# bristol_longshot.net
KiCad netlist of a schematic drawn in EAGLE
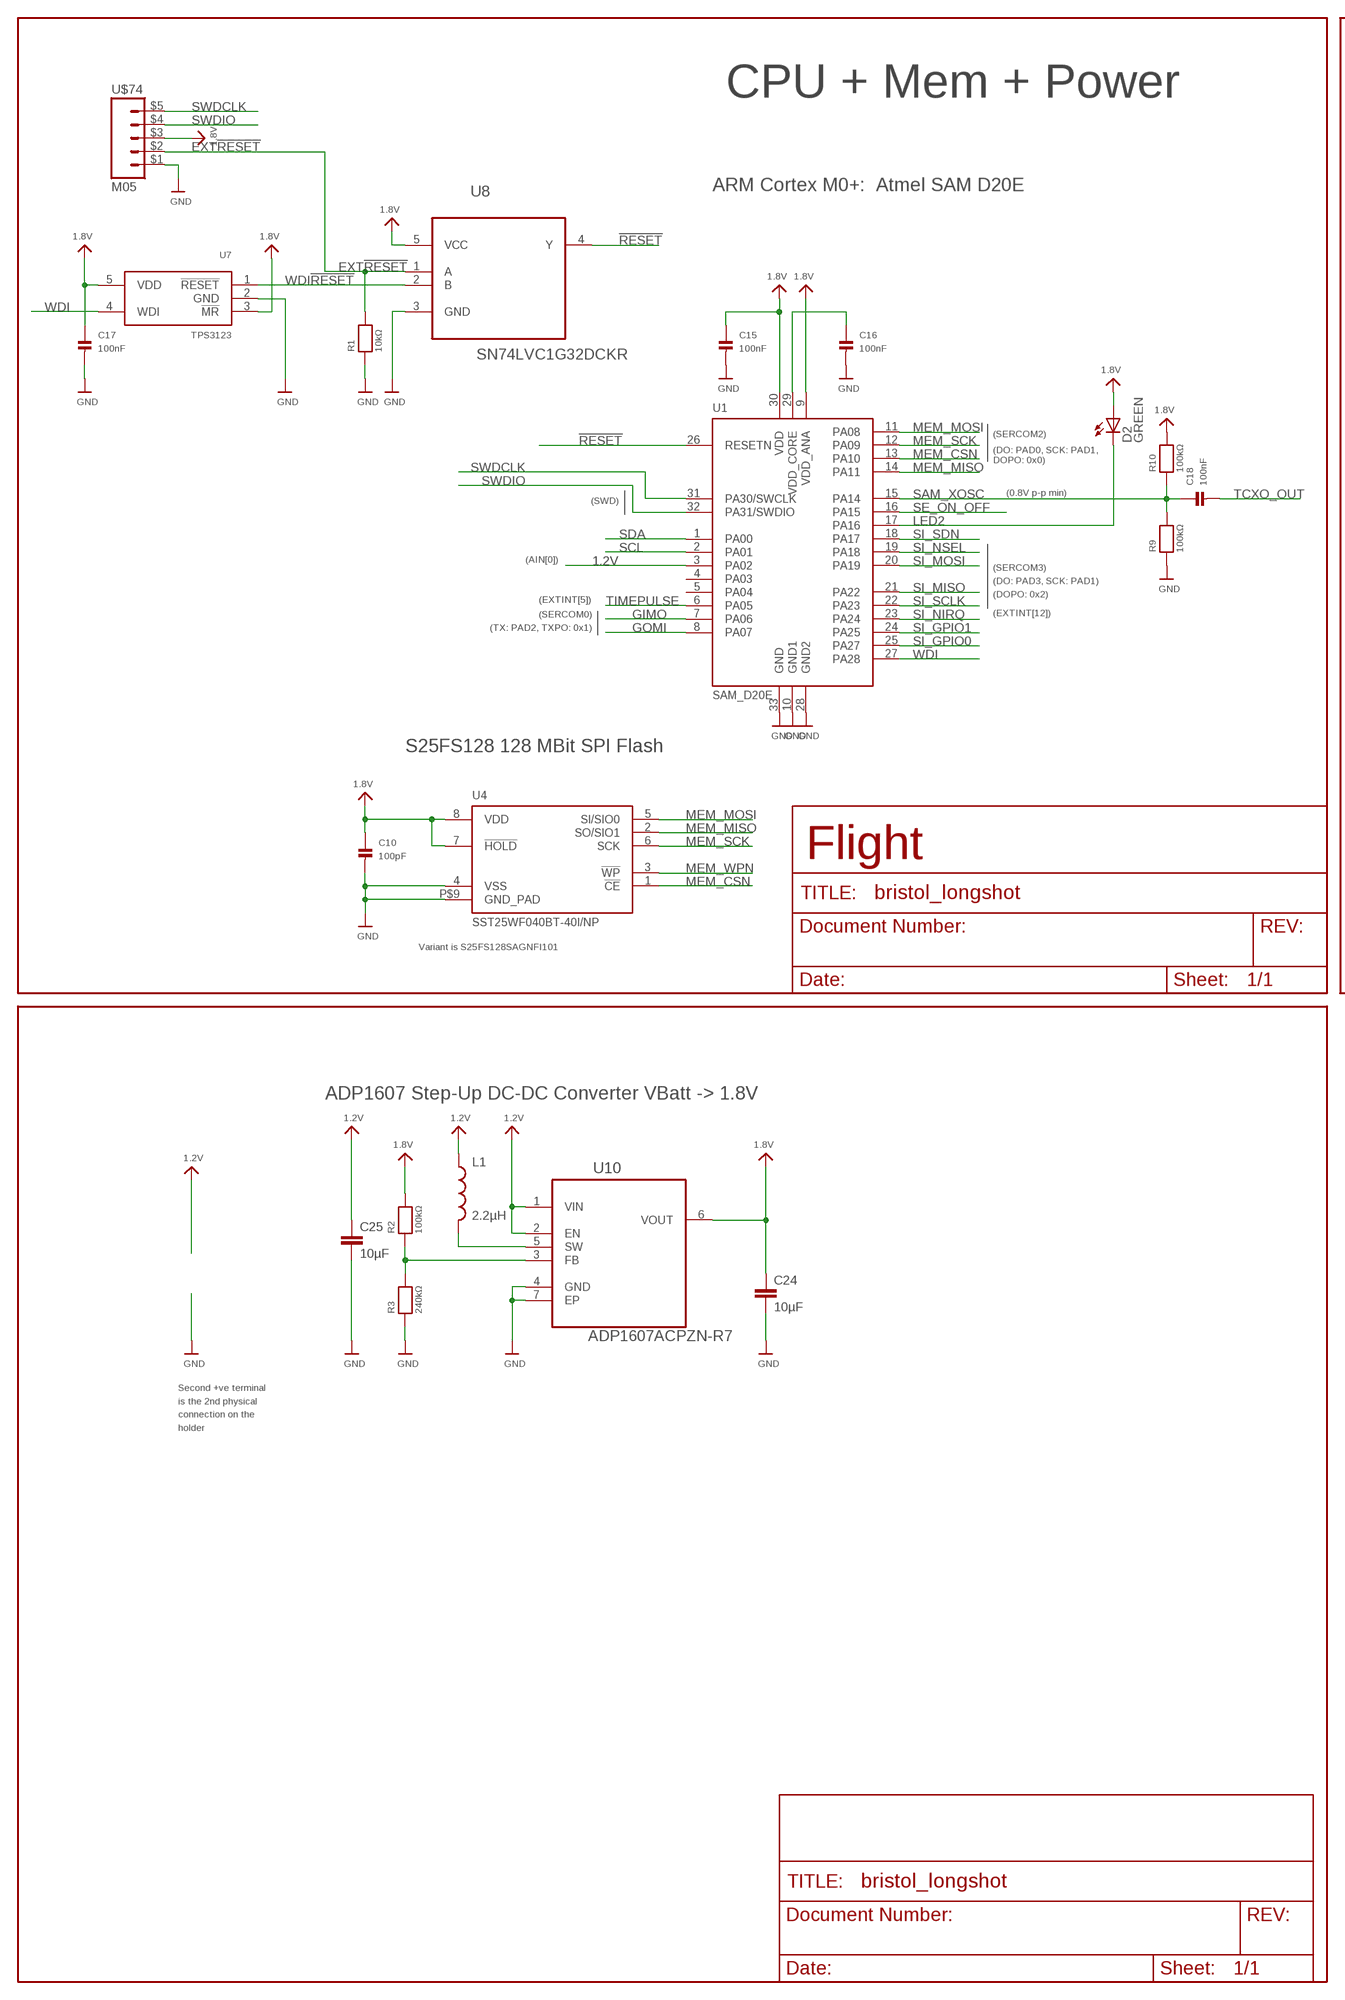
[diagram p0: schematic, sheet 1, part 1 of 2]
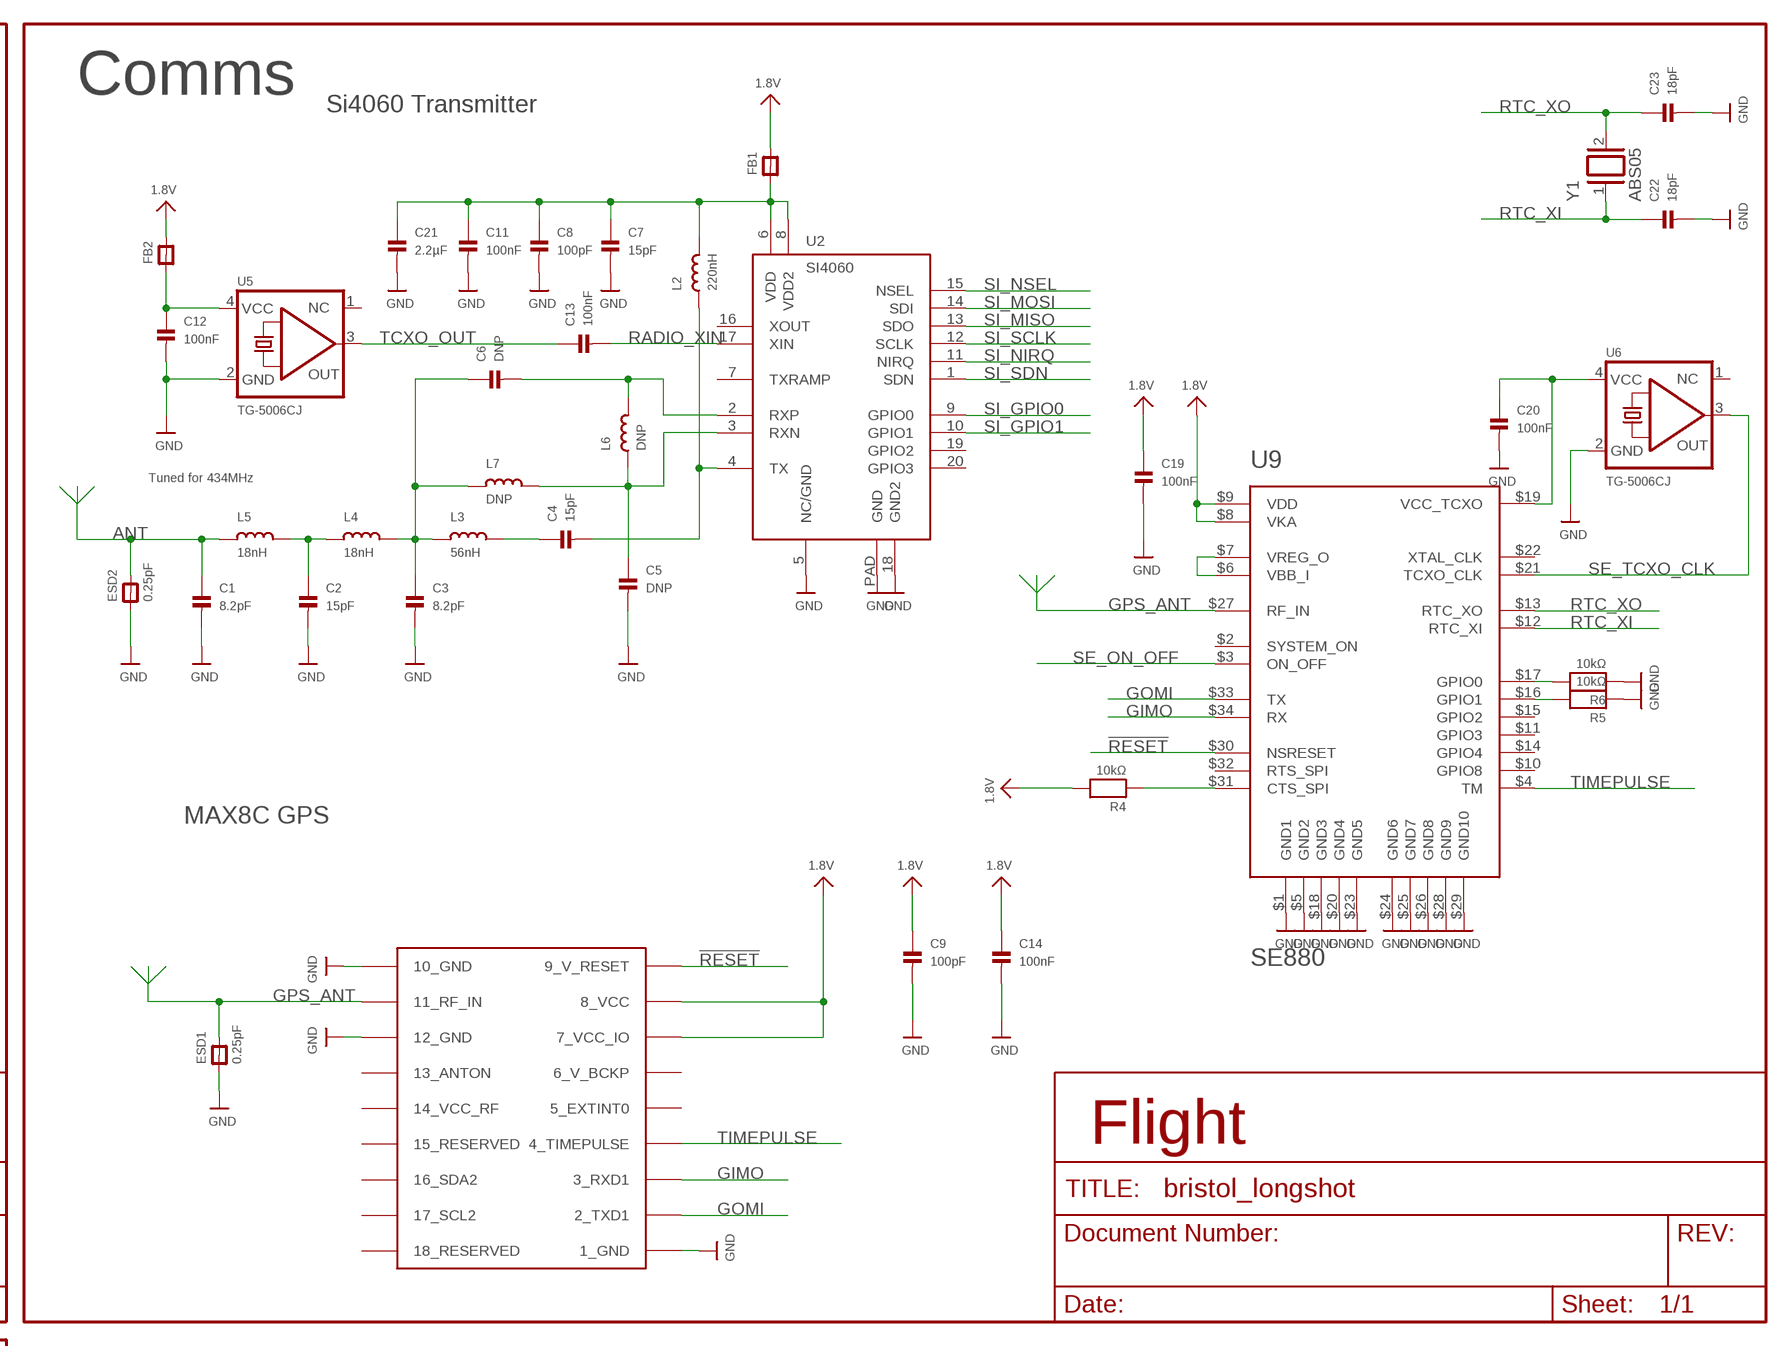
[diagram p1: schematic, sheet 1, part 2 of 2]

(export (version "E")
  (design (tool "Eeschema 10.0.6"))
  (components
    (comp (ref "C1")
      (value "8.2pF")
      (footprint "eagle-import:_0402")
      (libsource (lib "eagle-import") (part "CAP_CERAMIC_0402"))
    )
    (comp (ref "C2")
      (value "15pF")
      (footprint "eagle-import:_0402")
      (libsource (lib "eagle-import") (part "CAP_CERAMIC_0402"))
    )
    (comp (ref "C3")
      (value "8.2pF")
      (footprint "eagle-import:_0402")
      (libsource (lib "eagle-import") (part "CAP_CERAMIC_0402"))
    )
    (comp (ref "C4")
      (value "15pF")
      (footprint "eagle-import:_0402")
      (libsource (lib "eagle-import") (part "CAP_CERAMIC_0402"))
    )
    (comp (ref "C5")
      (value "DNP")
      (footprint "eagle-import:_0402")
      (libsource (lib "eagle-import") (part "CAP_CERAMIC_0402"))
    )
    (comp (ref "C6")
      (value "DNP")
      (footprint "eagle-import:_0402")
      (libsource (lib "eagle-import") (part "CAP_CERAMIC_0402"))
    )
    (comp (ref "C7")
      (value "15pF")
      (footprint "eagle-import:_0402")
      (libsource (lib "eagle-import") (part "CAP_CERAMIC_0402"))
    )
    (comp (ref "C8")
      (value "100pF")
      (footprint "eagle-import:_0402")
      (libsource (lib "eagle-import") (part "CAP_CERAMIC_0402"))
    )
    (comp (ref "C9")
      (value "100pF")
      (footprint "eagle-import:_0402")
      (libsource (lib "eagle-import") (part "CAP_CERAMIC_0402"))
    )
    (comp (ref "C10")
      (value "100pF")
      (footprint "eagle-import:_0402")
      (libsource (lib "eagle-import") (part "CAP_CERAMIC_0402"))
    )
    (comp (ref "C11")
      (value "100nF")
      (footprint "eagle-import:_0402")
      (libsource (lib "eagle-import") (part "CAP_CERAMIC_0402"))
    )
    (comp (ref "C12")
      (value "100nF")
      (footprint "eagle-import:_0402")
      (libsource (lib "eagle-import") (part "CAP_CERAMIC_0402"))
    )
    (comp (ref "C13")
      (value "100nF")
      (footprint "eagle-import:_0402")
      (libsource (lib "eagle-import") (part "CAP_CERAMIC_0402"))
    )
    (comp (ref "C14")
      (value "100nF")
      (footprint "eagle-import:_0402")
      (libsource (lib "eagle-import") (part "CAP_CERAMIC_0402"))
    )
    (comp (ref "C15")
      (value "100nF")
      (footprint "eagle-import:_0402")
      (libsource (lib "eagle-import") (part "CAP_CERAMIC_0402"))
    )
    (comp (ref "C16")
      (value "100nF")
      (footprint "eagle-import:_0402")
      (libsource (lib "eagle-import") (part "CAP_CERAMIC_0402"))
    )
    (comp (ref "C17")
      (value "100nF")
      (footprint "eagle-import:_0402")
      (libsource (lib "eagle-import") (part "CAP_CERAMIC_0402"))
    )
    (comp (ref "C18")
      (value "100nF")
      (footprint "eagle-import:_0402")
      (libsource (lib "eagle-import") (part "CAP_CERAMIC_0402"))
    )
    (comp (ref "C19")
      (value "100nF")
      (footprint "eagle-import:_0402")
      (libsource (lib "eagle-import") (part "CAP_CERAMIC_0402"))
    )
    (comp (ref "C20")
      (value "100nF")
      (footprint "eagle-import:_0402")
      (libsource (lib "eagle-import") (part "CAP_CERAMIC_0402"))
    )
    (comp (ref "C21")
      (value "2.2µF")
      (footprint "eagle-import:_0402")
      (libsource (lib "eagle-import") (part "CAP_CERAMIC_0402"))
    )
    (comp (ref "C22")
      (value "18pF")
      (footprint "eagle-import:_0402")
      (libsource (lib "eagle-import") (part "CAP_CERAMIC_0402"))
    )
    (comp (ref "C23")
      (value "18pF")
      (footprint "eagle-import:_0402")
      (libsource (lib "eagle-import") (part "CAP_CERAMIC_0402"))
    )
    (comp (ref "C24")
      (value "10µF")
      (footprint "eagle-import:C0603K")
      (libsource (lib "eagle-import") (part "C-EUC0603K"))
    )
    (comp (ref "C25")
      (value "10µF")
      (footprint "eagle-import:C0603K")
      (libsource (lib "eagle-import") (part "C-EUC0603K"))
    )
    (comp (ref "D2")
      (value "GREEN")
      (footprint "eagle-import:CHIPLED_0603")
      (libsource (lib "eagle-import") (part "LEDCHIPLED_0603"))
    )
    (comp (ref "ESD1")
      (value "0.25pF")
      (footprint "eagle-import:_0603MP")
      (libsource (lib "eagle-import") (part "FERRITE_0603MP"))
    )
    (comp (ref "ESD2")
      (value "0.25pF")
      (footprint "eagle-import:_0603MP")
      (libsource (lib "eagle-import") (part "FERRITE_0603MP"))
    )
    (comp (ref "FB1")
      (value "FERRITE_0402")
      (footprint "eagle-import:_0402")
      (libsource (lib "eagle-import") (part "FERRITE_0402"))
    )
    (comp (ref "FB2")
      (value "FERRITE_0402")
      (footprint "eagle-import:_0402")
      (libsource (lib "eagle-import") (part "FERRITE_0402"))
    )
    (comp (ref "L1")
      (value "2.2µH")
      (footprint "eagle-import:1007")
      (libsource (lib "eagle-import") (part "INDUCTOR1007"))
    )
    (comp (ref "L2")
      (value "220nH")
      (footprint "eagle-import:_0402")
      (libsource (lib "eagle-import") (part "INDUCTOR_0402"))
    )
    (comp (ref "L3")
      (value "56nH")
      (footprint "eagle-import:_0402")
      (libsource (lib "eagle-import") (part "INDUCTOR_0402"))
    )
    (comp (ref "L4")
      (value "18nH")
      (footprint "eagle-import:_0402")
      (libsource (lib "eagle-import") (part "INDUCTOR_0402"))
    )
    (comp (ref "L5")
      (value "18nH")
      (footprint "eagle-import:_0402")
      (libsource (lib "eagle-import") (part "INDUCTOR_0402"))
    )
    (comp (ref "L6")
      (value "DNP")
      (footprint "eagle-import:_0402")
      (libsource (lib "eagle-import") (part "INDUCTOR_0402"))
    )
    (comp (ref "L7")
      (value "DNP")
      (footprint "eagle-import:_0402")
      (libsource (lib "eagle-import") (part "INDUCTOR_0402"))
    )
    (comp (ref "R1")
      (value "10kΩ")
      (footprint "eagle-import:_0402")
      (libsource (lib "eagle-import") (part "RESISTOR_0402"))
    )
    (comp (ref "R2")
      (value "100kΩ")
      (footprint "eagle-import:_0402")
      (libsource (lib "eagle-import") (part "RESISTOR_0402"))
    )
    (comp (ref "R3")
      (value "240kΩ")
      (footprint "eagle-import:_0402")
      (libsource (lib "eagle-import") (part "RESISTOR_0402"))
    )
    (comp (ref "R4")
      (value "10kΩ")
      (footprint "eagle-import:_0402")
      (libsource (lib "eagle-import") (part "RESISTOR_0402"))
    )
    (comp (ref "R5")
      (value "10kΩ")
      (footprint "eagle-import:_0402")
      (libsource (lib "eagle-import") (part "RESISTOR_0402"))
    )
    (comp (ref "R6")
      (value "10kΩ")
      (footprint "eagle-import:_0402")
      (libsource (lib "eagle-import") (part "RESISTOR_0402"))
    )
    (comp (ref "R9")
      (value "100kΩ")
      (footprint "eagle-import:_0402")
      (libsource (lib "eagle-import") (part "RESISTOR_0402"))
    )
    (comp (ref "R10")
      (value "100kΩ")
      (footprint "eagle-import:_0402")
      (libsource (lib "eagle-import") (part "RESISTOR_0402"))
    )
    (comp (ref "U$74")
      (value "M05")
      (footprint "eagle-import:M05_SIDE")
      (libsource (lib "eagle-import") (part "M05"))
    )
    (comp (ref "U1")
      (value "SAM_D20E")
      (footprint "eagle-import:QFN32_5MM")
      (libsource (lib "eagle-import") (part "SAM_D20E"))
    )
    (comp (ref "U2")
      (value "SI4060")
      (footprint "eagle-import:QFN20")
      (libsource (lib "eagle-import") (part "SI4060"))
    )
    (comp (ref "U3")
      (value "UBLOX_MAX")
      (footprint "eagle-import:UBLOX_MAX")
      (libsource (lib "eagle-import") (part "UBLOX_MAX"))
    )
    (comp (ref "U4")
      (value "SST25WF040BT-40I/NP")
      (footprint "eagle-import:USON-8")
      (libsource (lib "eagle-import") (part "SST25WF040BT-40I/NP"))
    )
    (comp (ref "U5")
      (value "TG-5006CJ")
      (footprint "eagle-import:TC-5006CJ")
      (libsource (lib "eagle-import") (part "TG-5006CJ"))
    )
    (comp (ref "U6")
      (value "TG-5006CJ")
      (footprint "eagle-import:TC-5006CJ")
      (libsource (lib "eagle-import") (part "TG-5006CJ"))
    )
    (comp (ref "U7")
      (value "TPS3123")
      (footprint "eagle-import:SOT23-5")
      (libsource (lib "eagle-import") (part "TPS3123"))
    )
    (comp (ref "U8")
      (value "SN74LVC1G32DCKR")
      (footprint "eagle-import:SOT65P210X110-5N")
      (libsource (lib "eagle-import") (part "SN74LVC1G32DCKR"))
    )
    (comp (ref "U9")
      (value "SE880")
      (footprint "eagle-import:SE880")
      (libsource (lib "eagle-import") (part "SE880"))
    )
    (comp (ref "U10")
      (value "ADP1607ACPZN-R7")
      (footprint "eagle-import:DFN200X200X60-7N")
      (libsource (lib "eagle-import") (part "ADP1607ACPZN-R7"))
    )
    (comp (ref "Y1")
      (value "ABS05")
      (footprint "eagle-import:ABS05")
      (libsource (lib "eagle-import") (part "ABS05"))
    )
  )
  (nets
    (net (code "1") (name "/ANT") (class "Default")
      (node (ref "C1") (pin "1") (pinfunction "P$1_1") (pintype "passive"))
      (node (ref "ESD2") (pin "2") (pinfunction "P$2_2") (pintype "passive"))
      (node (ref "L5") (pin "1") (pinfunction "1_1") (pintype "passive"))
    )
    (net (code "2") (name "/EXT~{RESET}") (class "Default")
      (node (ref "R1") (pin "2") (pinfunction "2_2") (pintype "passive"))
      (node (ref "U$74") (pin "$2") (pinfunction "2_$2") (pintype "passive"))
      (node (ref "U8") (pin "1") (pinfunction "A_1") (pintype "input"))
    )
    (net (code "3") (name "/GIMO") (class "Default")
      (node (ref "U1") (pin "7") (pinfunction "PA06_7") (pintype "bidirectional"))
      (node (ref "U3") (pin "3_RXD1") (pinfunction "3_RXD1_3_RXD1") (pintype "bidirectional"))
      (node (ref "U9") (pin "$34") (pinfunction "RX_$34") (pintype "bidirectional"))
    )
    (net (code "4") (name "/GOMI") (class "Default")
      (node (ref "U1") (pin "8") (pinfunction "PA07_8") (pintype "bidirectional"))
      (node (ref "U3") (pin "2_TXD1") (pinfunction "2_TXD1_2_TXD1") (pintype "bidirectional"))
      (node (ref "U9") (pin "$33") (pinfunction "TX_$33") (pintype "bidirectional"))
    )
    (net (code "5") (name "/GPS_ANT") (class "Default")
      (node (ref "ESD1") (pin "2") (pinfunction "P$2_2") (pintype "passive"))
      (node (ref "U3") (pin "11_RF_IN") (pinfunction "11_RF_IN_11_RF_IN") (pintype "bidirectional"))
      (node (ref "U9") (pin "$27") (pinfunction "RF_IN_$27") (pintype "bidirectional"))
    )
    (net (code "6") (name "/LED2") (class "Default")
      (node (ref "D2") (pin "C") (pinfunction "C_C") (pintype "passive"))
      (node (ref "U1") (pin "17") (pinfunction "PA16_17") (pintype "bidirectional"))
    )
    (net (code "7") (name "/MEM_CSN") (class "Default")
      (node (ref "U1") (pin "13") (pinfunction "PA10_13") (pintype "bidirectional"))
      (node (ref "U4") (pin "1") (pinfunction "~{CE}_1") (pintype "input"))
    )
    (net (code "8") (name "/MEM_MISO") (class "Default")
      (node (ref "U1") (pin "14") (pinfunction "PA11_14") (pintype "bidirectional"))
      (node (ref "U4") (pin "2") (pinfunction "SO/SIO1_2") (pintype "output"))
    )
    (net (code "9") (name "/MEM_MOSI") (class "Default")
      (node (ref "U1") (pin "11") (pinfunction "PA08_11") (pintype "bidirectional"))
      (node (ref "U4") (pin "5") (pinfunction "SI/SIO0_5") (pintype "bidirectional"))
    )
    (net (code "10") (name "/MEM_SCK") (class "Default")
      (node (ref "U1") (pin "12") (pinfunction "PA09_12") (pintype "bidirectional"))
      (node (ref "U4") (pin "6") (pinfunction "SCK_6") (pintype "input"))
    )
    (net (code "11") (name "/MEM_WPN") (class "Default")
      (node (ref "U4") (pin "3") (pinfunction "~{WP}_3") (pintype "output"))
    )
    (net (code "12") (name "/RADIO_XIN") (class "Default")
      (node (ref "C13") (pin "2") (pinfunction "P$2_2") (pintype "passive"))
      (node (ref "U2") (pin "17") (pinfunction "XIN_17") (pintype "input"))
    )
    (net (code "13") (name "/RTC_XI") (class "Default")
      (node (ref "C22") (pin "1") (pinfunction "P$1_1") (pintype "passive"))
      (node (ref "U9") (pin "$12") (pinfunction "RTC_XI_$12") (pintype "bidirectional"))
      (node (ref "Y1") (pin "1") (pinfunction "1_1") (pintype "passive"))
    )
    (net (code "14") (name "/RTC_XO") (class "Default")
      (node (ref "C23") (pin "1") (pinfunction "P$1_1") (pintype "passive"))
      (node (ref "U9") (pin "$13") (pinfunction "RTC_XO_$13") (pintype "bidirectional"))
      (node (ref "Y1") (pin "2") (pinfunction "2_2") (pintype "passive"))
    )
    (net (code "15") (name "/SAM_XOSC") (class "Default")
      (node (ref "C18") (pin "1") (pinfunction "P$1_1") (pintype "passive"))
      (node (ref "R10") (pin "1") (pinfunction "1_1") (pintype "passive"))
      (node (ref "R9") (pin "2") (pinfunction "2_2") (pintype "passive"))
      (node (ref "U1") (pin "15") (pinfunction "PA14_15") (pintype "bidirectional"))
    )
    (net (code "16") (name "/SCL") (class "Default")
      (node (ref "U1") (pin "2") (pinfunction "PA01_2") (pintype "bidirectional"))
    )
    (net (code "17") (name "/SDA") (class "Default")
      (node (ref "U1") (pin "1") (pinfunction "PA00_1") (pintype "bidirectional"))
    )
    (net (code "18") (name "/SE_ON_OFF") (class "Default")
      (node (ref "U1") (pin "16") (pinfunction "PA15_16") (pintype "bidirectional"))
      (node (ref "U9") (pin "$3") (pinfunction "ON_OFF_$3") (pintype "bidirectional"))
    )
    (net (code "19") (name "/SE_TCXO_CLK") (class "Default")
      (node (ref "U6") (pin "3") (pinfunction "OUT_3") (pintype "output"))
      (node (ref "U9") (pin "$21") (pinfunction "TCXO_CLK_$21") (pintype "bidirectional"))
    )
    (net (code "20") (name "/SI_GPIO0") (class "Default")
      (node (ref "U1") (pin "25") (pinfunction "PA27_25") (pintype "bidirectional"))
      (node (ref "U2") (pin "9") (pinfunction "GPIO0_9") (pintype "bidirectional"))
    )
    (net (code "21") (name "/SI_GPIO1") (class "Default")
      (node (ref "U1") (pin "24") (pinfunction "PA25_24") (pintype "bidirectional"))
      (node (ref "U2") (pin "10") (pinfunction "GPIO1_10") (pintype "bidirectional"))
    )
    (net (code "22") (name "/SI_MISO") (class "Default")
      (node (ref "U1") (pin "21") (pinfunction "PA22_21") (pintype "bidirectional"))
      (node (ref "U2") (pin "13") (pinfunction "SDO_13") (pintype "output"))
    )
    (net (code "23") (name "/SI_MOSI") (class "Default")
      (node (ref "U1") (pin "20") (pinfunction "PA19_20") (pintype "bidirectional"))
      (node (ref "U2") (pin "14") (pinfunction "SDI_14") (pintype "bidirectional"))
    )
    (net (code "24") (name "/SI_NIRQ") (class "Default")
      (node (ref "U1") (pin "23") (pinfunction "PA24_23") (pintype "bidirectional"))
      (node (ref "U2") (pin "11") (pinfunction "NIRQ_11") (pintype "output"))
    )
    (net (code "25") (name "/SI_NSEL") (class "Default")
      (node (ref "U1") (pin "19") (pinfunction "PA18_19") (pintype "bidirectional"))
      (node (ref "U2") (pin "15") (pinfunction "NSEL_15") (pintype "input"))
    )
    (net (code "26") (name "/SI_SCLK") (class "Default")
      (node (ref "U1") (pin "22") (pinfunction "PA23_22") (pintype "bidirectional"))
      (node (ref "U2") (pin "12") (pinfunction "SCLK_12") (pintype "input"))
    )
    (net (code "27") (name "/SI_SDN") (class "Default")
      (node (ref "U1") (pin "18") (pinfunction "PA17_18") (pintype "bidirectional"))
      (node (ref "U2") (pin "1") (pinfunction "SDN_1") (pintype "input"))
    )
    (net (code "28") (name "/SWDCLK") (class "Default")
      (node (ref "U$74") (pin "$5") (pinfunction "5_$5") (pintype "passive"))
      (node (ref "U1") (pin "31") (pinfunction "PA30/SWCLK_31") (pintype "bidirectional"))
    )
    (net (code "29") (name "/SWDIO") (class "Default")
      (node (ref "U$74") (pin "$4") (pinfunction "4_$4") (pintype "passive"))
      (node (ref "U1") (pin "32") (pinfunction "PA31/SWDIO_32") (pintype "bidirectional"))
    )
    (net (code "30") (name "/TCXO_OUT") (class "Default")
      (node (ref "C13") (pin "1") (pinfunction "P$1_1") (pintype "passive"))
      (node (ref "C18") (pin "2") (pinfunction "P$2_2") (pintype "passive"))
      (node (ref "U5") (pin "3") (pinfunction "OUT_3") (pintype "output"))
    )
    (net (code "31") (name "/TIMEPULSE") (class "Default")
      (node (ref "U1") (pin "6") (pinfunction "PA05_6") (pintype "bidirectional"))
      (node (ref "U3") (pin "4_TIMEPULSE") (pinfunction "4_TIMEPULSE_4_TIMEPULSE") (pintype "bidirectional"))
      (node (ref "U9") (pin "$4") (pinfunction "TM_$4") (pintype "bidirectional"))
    )
    (net (code "32") (name "/WDI") (class "Default")
      (node (ref "U1") (pin "27") (pinfunction "PA28_27") (pintype "bidirectional"))
      (node (ref "U7") (pin "4") (pinfunction "WDI_4") (pintype "bidirectional"))
    )
    (net (code "33") (name "/WDI~{RESET}") (class "Default")
      (node (ref "U7") (pin "1") (pinfunction "~{RESET}_1") (pintype "bidirectional"))
      (node (ref "U8") (pin "2") (pinfunction "B_2") (pintype "input"))
    )
    (net (code "34") (name "/~{RESET}") (class "Default")
      (node (ref "U1") (pin "26") (pinfunction "RESETN_26") (pintype "input"))
      (node (ref "U3") (pin "9_V_RESET") (pinfunction "9_V_RESET_9_V_RESET") (pintype "power_in"))
      (node (ref "U8") (pin "4") (pinfunction "Y_4") (pintype "output"))
      (node (ref "U9") (pin "$30") (pinfunction "NSRESET_$30") (pintype "bidirectional"))
    )
    (net (code "35") (name "1.2V") (class "Default")
      (node (ref "C25") (pin "1") (pinfunction "1_1") (pintype "passive"))
      (node (ref "L1") (pin "1") (pinfunction "1_1") (pintype "passive"))
      (node (ref "U1") (pin "3") (pinfunction "PA02_3") (pintype "bidirectional"))
      (node (ref "U10") (pin "1") (pinfunction "VIN_1") (pintype "power_in"))
      (node (ref "U10") (pin "2") (pinfunction "EN_2") (pintype "input"))
    )
    (net (code "36") (name "1.8V") (class "Default")
      (node (ref "C10") (pin "1") (pinfunction "P$1_1") (pintype "passive"))
      (node (ref "C14") (pin "1") (pinfunction "P$1_1") (pintype "passive"))
      (node (ref "C15") (pin "1") (pinfunction "P$1_1") (pintype "passive"))
      (node (ref "C17") (pin "1") (pinfunction "P$1_1") (pintype "passive"))
      (node (ref "C19") (pin "1") (pinfunction "P$1_1") (pintype "passive"))
      (node (ref "C24") (pin "1") (pinfunction "1_1") (pintype "passive"))
      (node (ref "C9") (pin "1") (pinfunction "P$1_1") (pintype "passive"))
      (node (ref "D2") (pin "A") (pinfunction "A_A") (pintype "passive"))
      (node (ref "FB1") (pin "2") (pinfunction "P$2_2") (pintype "passive"))
      (node (ref "FB2") (pin "2") (pinfunction "P$2_2") (pintype "passive"))
      (node (ref "R10") (pin "2") (pinfunction "2_2") (pintype "passive"))
      (node (ref "R2") (pin "2") (pinfunction "2_2") (pintype "passive"))
      (node (ref "R4") (pin "2") (pinfunction "2_2") (pintype "passive"))
      (node (ref "U$74") (pin "$3") (pinfunction "3_$3") (pintype "passive"))
      (node (ref "U1") (pin "30") (pinfunction "VDD_30") (pintype "power_in"))
      (node (ref "U1") (pin "9") (pinfunction "VDD_ANA_9") (pintype "power_in"))
      (node (ref "U10") (pin "6") (pinfunction "VOUT_6") (pintype "output"))
      (node (ref "U3") (pin "7_VCC_IO") (pinfunction "7_VCC_IO_7_VCC_IO") (pintype "power_in"))
      (node (ref "U3") (pin "8_VCC") (pinfunction "8_VCC_8_VCC") (pintype "power_in"))
      (node (ref "U4") (pin "7") (pinfunction "~{HOLD}_7") (pintype "output"))
      (node (ref "U4") (pin "8") (pinfunction "VDD_8") (pintype "power_in"))
      (node (ref "U7") (pin "3") (pinfunction "~{MR}_3") (pintype "bidirectional"))
      (node (ref "U7") (pin "5") (pinfunction "VDD_5") (pintype "bidirectional"))
      (node (ref "U8") (pin "5") (pinfunction "VCC_5") (pintype "power_in"))
      (node (ref "U9") (pin "$8") (pinfunction "VKA_$8") (pintype "bidirectional"))
      (node (ref "U9") (pin "$9") (pinfunction "VDD_$9") (pintype "bidirectional"))
    )
    (net (code "37") (name "GND") (class "Default")
      (node (ref "C1") (pin "2") (pinfunction "P$2_2") (pintype "passive"))
      (node (ref "C10") (pin "2") (pinfunction "P$2_2") (pintype "passive"))
      (node (ref "C11") (pin "2") (pinfunction "P$2_2") (pintype "passive"))
      (node (ref "C12") (pin "2") (pinfunction "P$2_2") (pintype "passive"))
      (node (ref "C14") (pin "2") (pinfunction "P$2_2") (pintype "passive"))
      (node (ref "C15") (pin "2") (pinfunction "P$2_2") (pintype "passive"))
      (node (ref "C16") (pin "2") (pinfunction "P$2_2") (pintype "passive"))
      (node (ref "C17") (pin "2") (pinfunction "P$2_2") (pintype "passive"))
      (node (ref "C19") (pin "2") (pinfunction "P$2_2") (pintype "passive"))
      (node (ref "C2") (pin "2") (pinfunction "P$2_2") (pintype "passive"))
      (node (ref "C20") (pin "2") (pinfunction "P$2_2") (pintype "passive"))
      (node (ref "C21") (pin "2") (pinfunction "P$2_2") (pintype "passive"))
      (node (ref "C22") (pin "2") (pinfunction "P$2_2") (pintype "passive"))
      (node (ref "C23") (pin "2") (pinfunction "P$2_2") (pintype "passive"))
      (node (ref "C24") (pin "2") (pinfunction "2_2") (pintype "passive"))
      (node (ref "C25") (pin "2") (pinfunction "2_2") (pintype "passive"))
      (node (ref "C3") (pin "2") (pinfunction "P$2_2") (pintype "passive"))
      (node (ref "C5") (pin "2") (pinfunction "P$2_2") (pintype "passive"))
      (node (ref "C7") (pin "2") (pinfunction "P$2_2") (pintype "passive"))
      (node (ref "C8") (pin "2") (pinfunction "P$2_2") (pintype "passive"))
      (node (ref "C9") (pin "2") (pinfunction "P$2_2") (pintype "passive"))
      (node (ref "ESD1") (pin "1") (pinfunction "P$1_1") (pintype "passive"))
      (node (ref "ESD2") (pin "1") (pinfunction "P$1_1") (pintype "passive"))
      (node (ref "R1") (pin "1") (pinfunction "1_1") (pintype "passive"))
      (node (ref "R3") (pin "1") (pinfunction "1_1") (pintype "passive"))
      (node (ref "R5") (pin "1") (pinfunction "1_1") (pintype "passive"))
      (node (ref "R6") (pin "1") (pinfunction "1_1") (pintype "passive"))
      (node (ref "R9") (pin "1") (pinfunction "1_1") (pintype "passive"))
      (node (ref "U$74") (pin "$1") (pinfunction "1_$1") (pintype "passive"))
      (node (ref "U1") (pin "10") (pinfunction "GND1_10") (pintype "power_in"))
      (node (ref "U1") (pin "28") (pinfunction "GND2_28") (pintype "power_in"))
      (node (ref "U1") (pin "33") (pinfunction "GND_33") (pintype "power_in"))
      (node (ref "U10") (pin "4") (pinfunction "GND_4") (pintype "power_in"))
      (node (ref "U10") (pin "7") (pinfunction "EP_7") (pintype "passive"))
      (node (ref "U2") (pin "18") (pinfunction "GND2_18") (pintype "power_in"))
      (node (ref "U2") (pin "5") (pinfunction "NC/GND_5") (pintype "bidirectional"))
      (node (ref "U2") (pin "PAD") (pinfunction "GND_PAD") (pintype "power_in"))
      (node (ref "U3") (pin "10_GND") (pinfunction "10_GND_10_GND") (pintype "power_in"))
      (node (ref "U3") (pin "12_GND") (pinfunction "12_GND_12_GND") (pintype "power_in"))
      (node (ref "U3") (pin "1_GND") (pinfunction "1_GND_1_GND") (pintype "power_in"))
      (node (ref "U4") (pin "4") (pinfunction "VSS_4") (pintype "power_in"))
      (node (ref "U4") (pin "P$9") (pinfunction "GND_PAD_P$9") (pintype "power_in"))
      (node (ref "U5") (pin "2") (pinfunction "GND_2") (pintype "power_in"))
      (node (ref "U6") (pin "2") (pinfunction "GND_2") (pintype "power_in"))
      (node (ref "U7") (pin "2") (pinfunction "GND_2") (pintype "bidirectional"))
      (node (ref "U8") (pin "3") (pinfunction "GND_3") (pintype "passive"))
      (node (ref "U9") (pin "$1") (pinfunction "GND1_$1") (pintype "bidirectional"))
      (node (ref "U9") (pin "$18") (pinfunction "GND3_$18") (pintype "bidirectional"))
      (node (ref "U9") (pin "$20") (pinfunction "GND4_$20") (pintype "bidirectional"))
      (node (ref "U9") (pin "$23") (pinfunction "GND5_$23") (pintype "bidirectional"))
      (node (ref "U9") (pin "$24") (pinfunction "GND6_$24") (pintype "bidirectional"))
      (node (ref "U9") (pin "$25") (pinfunction "GND7_$25") (pintype "bidirectional"))
      (node (ref "U9") (pin "$26") (pinfunction "GND8_$26") (pintype "bidirectional"))
      (node (ref "U9") (pin "$28") (pinfunction "GND9_$28") (pintype "bidirectional"))
      (node (ref "U9") (pin "$29") (pinfunction "GND10_$29") (pintype "bidirectional"))
      (node (ref "U9") (pin "$5") (pinfunction "GND2_$5") (pintype "bidirectional"))
    )
    (net (code "38") (name "Net-(C2-P$1)") (class "Default")
      (node (ref "C2") (pin "1") (pinfunction "P$1_1") (pintype "passive"))
      (node (ref "L4") (pin "1") (pinfunction "1_1") (pintype "passive"))
      (node (ref "L5") (pin "2") (pinfunction "2_2") (pintype "passive"))
    )
    (net (code "39") (name "Net-(C3-P$1)") (class "Default")
      (node (ref "C3") (pin "1") (pinfunction "P$1_1") (pintype "passive"))
      (node (ref "C6") (pin "1") (pinfunction "P$1_1") (pintype "passive"))
      (node (ref "L3") (pin "1") (pinfunction "1_1") (pintype "passive"))
      (node (ref "L4") (pin "2") (pinfunction "2_2") (pintype "passive"))
      (node (ref "L7") (pin "1") (pinfunction "1_1") (pintype "passive"))
    )
    (net (code "40") (name "Net-(C4-P$1)") (class "Default")
      (node (ref "C4") (pin "1") (pinfunction "P$1_1") (pintype "passive"))
      (node (ref "L3") (pin "2") (pinfunction "2_2") (pintype "passive"))
    )
    (net (code "41") (name "Net-(C4-P$2)") (class "Default")
      (node (ref "C4") (pin "2") (pinfunction "P$2_2") (pintype "passive"))
      (node (ref "L2") (pin "1") (pinfunction "1_1") (pintype "passive"))
      (node (ref "U2") (pin "4") (pinfunction "TX_4") (pintype "output"))
    )
    (net (code "42") (name "Net-(C5-P$1)") (class "Default")
      (node (ref "C5") (pin "1") (pinfunction "P$1_1") (pintype "passive"))
      (node (ref "L6") (pin "1") (pinfunction "1_1") (pintype "passive"))
      (node (ref "L7") (pin "2") (pinfunction "2_2") (pintype "passive"))
      (node (ref "U2") (pin "3") (pinfunction "RXN_3") (pintype "input"))
    )
    (net (code "43") (name "Net-(C6-P$2)") (class "Default")
      (node (ref "C6") (pin "2") (pinfunction "P$2_2") (pintype "passive"))
      (node (ref "L6") (pin "2") (pinfunction "2_2") (pintype "passive"))
      (node (ref "U2") (pin "2") (pinfunction "RXP_2") (pintype "input"))
    )
    (net (code "44") (name "Net-(C11-P$1)") (class "Default")
      (node (ref "C11") (pin "1") (pinfunction "P$1_1") (pintype "passive"))
      (node (ref "C21") (pin "1") (pinfunction "P$1_1") (pintype "passive"))
      (node (ref "C7") (pin "1") (pinfunction "P$1_1") (pintype "passive"))
      (node (ref "C8") (pin "1") (pinfunction "P$1_1") (pintype "passive"))
      (node (ref "FB1") (pin "1") (pinfunction "P$1_1") (pintype "passive"))
      (node (ref "L2") (pin "2") (pinfunction "2_2") (pintype "passive"))
      (node (ref "U2") (pin "6") (pinfunction "VDD_6") (pintype "power_in"))
      (node (ref "U2") (pin "8") (pinfunction "VDD2_8") (pintype "power_in"))
    )
    (net (code "45") (name "Net-(C12-P$1)") (class "Default")
      (node (ref "C12") (pin "1") (pinfunction "P$1_1") (pintype "passive"))
      (node (ref "FB2") (pin "1") (pinfunction "P$1_1") (pintype "passive"))
      (node (ref "U5") (pin "4") (pinfunction "VCC_4") (pintype "power_in"))
    )
    (net (code "46") (name "Net-(C16-P$1)") (class "Default")
      (node (ref "C16") (pin "1") (pinfunction "P$1_1") (pintype "passive"))
      (node (ref "U1") (pin "29") (pinfunction "VDD_CORE_29") (pintype "power_in"))
    )
    (net (code "47") (name "Net-(C20-P$1)") (class "Default")
      (node (ref "C20") (pin "1") (pinfunction "P$1_1") (pintype "passive"))
      (node (ref "U6") (pin "4") (pinfunction "VCC_4") (pintype "power_in"))
      (node (ref "U9") (pin "$19") (pinfunction "VCC_TCXO_$19") (pintype "bidirectional"))
    )
    (net (code "48") (name "Net-(U9-CTS_SPI)") (class "Default")
      (node (ref "R4") (pin "1") (pinfunction "1_1") (pintype "passive"))
      (node (ref "U9") (pin "$31") (pinfunction "CTS_SPI_$31") (pintype "bidirectional"))
    )
    (net (code "49") (name "Net-(U9-GPIO0)") (class "Default")
      (node (ref "R6") (pin "2") (pinfunction "2_2") (pintype "passive"))
      (node (ref "U9") (pin "$17") (pinfunction "GPIO0_$17") (pintype "bidirectional"))
    )
    (net (code "50") (name "Net-(U9-GPIO1)") (class "Default")
      (node (ref "R5") (pin "2") (pinfunction "2_2") (pintype "passive"))
      (node (ref "U9") (pin "$16") (pinfunction "GPIO1_$16") (pintype "bidirectional"))
    )
    (net (code "51") (name "Net-(U9-VBB_I)") (class "Default")
      (node (ref "U9") (pin "$6") (pinfunction "VBB_I_$6") (pintype "bidirectional"))
      (node (ref "U9") (pin "$7") (pinfunction "VREG_O_$7") (pintype "bidirectional"))
    )
    (net (code "52") (name "Net-(U10-FB)") (class "Default")
      (node (ref "R2") (pin "1") (pinfunction "1_1") (pintype "passive"))
      (node (ref "R3") (pin "2") (pinfunction "2_2") (pintype "passive"))
      (node (ref "U10") (pin "3") (pinfunction "FB_3") (pintype "passive"))
    )
    (net (code "53") (name "Net-(U10-SW)") (class "Default")
      (node (ref "L1") (pin "2") (pinfunction "2_2") (pintype "passive"))
      (node (ref "U10") (pin "5") (pinfunction "SW_5") (pintype "passive"))
    )
    (net (code "54") (name "unconnected-(U1-PA03-Pad4)") (class "Default")
      (node (ref "U1") (pin "4") (pinfunction "PA03_4") (pintype "bidirectional"))
    )
    (net (code "55") (name "unconnected-(U1-PA04-Pad5)") (class "Default")
      (node (ref "U1") (pin "5") (pinfunction "PA04_5") (pintype "bidirectional"))
    )
    (net (code "56") (name "unconnected-(U2-GPIO2-Pad19)") (class "Default")
      (node (ref "U2") (pin "19") (pinfunction "GPIO2_19") (pintype "bidirectional"))
    )
    (net (code "57") (name "unconnected-(U2-GPIO3-Pad20)") (class "Default")
      (node (ref "U2") (pin "20") (pinfunction "GPIO3_20") (pintype "bidirectional"))
    )
    (net (code "58") (name "unconnected-(U2-TXRAMP-Pad7)") (class "Default")
      (node (ref "U2") (pin "7") (pinfunction "TXRAMP_7") (pintype "bidirectional"))
    )
    (net (code "59") (name "unconnected-(U2-XOUT-Pad16)") (class "Default")
      (node (ref "U2") (pin "16") (pinfunction "XOUT_16") (pintype "output"))
    )
    (net (code "60") (name "unconnected-(U3-Pad5_EXTINT0)") (class "Default")
      (node (ref "U3") (pin "5_EXTINT0") (pinfunction "5_EXTINT0_5_EXTINT0") (pintype "bidirectional"))
    )
    (net (code "61") (name "unconnected-(U3-Pad6_V_BCKP)") (class "Default")
      (node (ref "U3") (pin "6_V_BCKP") (pinfunction "6_V_BCKP_6_V_BCKP") (pintype "bidirectional"))
    )
    (net (code "62") (name "unconnected-(U3-Pad13_ANTON)") (class "Default")
      (node (ref "U3") (pin "13_ANTON") (pinfunction "13_ANTON_13_ANTON") (pintype "bidirectional"))
    )
    (net (code "63") (name "unconnected-(U3-Pad14_VCC_RF)") (class "Default")
      (node (ref "U3") (pin "14_VCC_RF") (pinfunction "14_VCC_RF_14_VCC_RF") (pintype "bidirectional"))
    )
    (net (code "64") (name "unconnected-(U3-Pad15_RESERVED)") (class "Default")
      (node (ref "U3") (pin "15_RESERVED") (pinfunction "15_RESERVED_15_RESERVED") (pintype "bidirectional"))
    )
    (net (code "65") (name "unconnected-(U3-Pad16_SDA2)") (class "Default")
      (node (ref "U3") (pin "16_SDA2") (pinfunction "16_SDA2_16_SDA2") (pintype "bidirectional"))
    )
    (net (code "66") (name "unconnected-(U3-Pad17_SCL2)") (class "Default")
      (node (ref "U3") (pin "17_SCL2") (pinfunction "17_SCL2_17_SCL2") (pintype "bidirectional"))
    )
    (net (code "67") (name "unconnected-(U3-Pad18_RESERVED)") (class "Default")
      (node (ref "U3") (pin "18_RESERVED") (pinfunction "18_RESERVED_18_RESERVED") (pintype "bidirectional"))
    )
    (net (code "68") (name "unconnected-(U5-NC-Pad1)") (class "Default")
      (node (ref "U5") (pin "1") (pinfunction "NC_1") (pintype "no_connect"))
    )
    (net (code "69") (name "unconnected-(U6-NC-Pad1)") (class "Default")
      (node (ref "U6") (pin "1") (pinfunction "NC_1") (pintype "no_connect"))
    )
    (net (code "70") (name "unconnected-(U9-GPIO2-Pad$15)") (class "Default")
      (node (ref "U9") (pin "$15") (pinfunction "GPIO2_$15") (pintype "bidirectional"))
    )
    (net (code "71") (name "unconnected-(U9-GPIO3-Pad$11)") (class "Default")
      (node (ref "U9") (pin "$11") (pinfunction "GPIO3_$11") (pintype "bidirectional"))
    )
    (net (code "72") (name "unconnected-(U9-GPIO4-Pad$14)") (class "Default")
      (node (ref "U9") (pin "$14") (pinfunction "GPIO4_$14") (pintype "bidirectional"))
    )
    (net (code "73") (name "unconnected-(U9-GPIO8-Pad$10)") (class "Default")
      (node (ref "U9") (pin "$10") (pinfunction "GPIO8_$10") (pintype "bidirectional"))
    )
    (net (code "74") (name "unconnected-(U9-RTS_SPI-Pad$32)") (class "Default")
      (node (ref "U9") (pin "$32") (pinfunction "RTS_SPI_$32") (pintype "bidirectional"))
    )
    (net (code "75") (name "unconnected-(U9-SYSTEM_ON-Pad$2)") (class "Default")
      (node (ref "U9") (pin "$2") (pinfunction "SYSTEM_ON_$2") (pintype "bidirectional"))
    )
    (net (code "76") (name "unconnected-(U9-XTAL_CLK-Pad$22)") (class "Default")
      (node (ref "U9") (pin "$22") (pinfunction "XTAL_CLK_$22") (pintype "bidirectional"))
    )
  )
)
